# Clock.net
KiCad netlist of a schematic drawn in Altium Designer
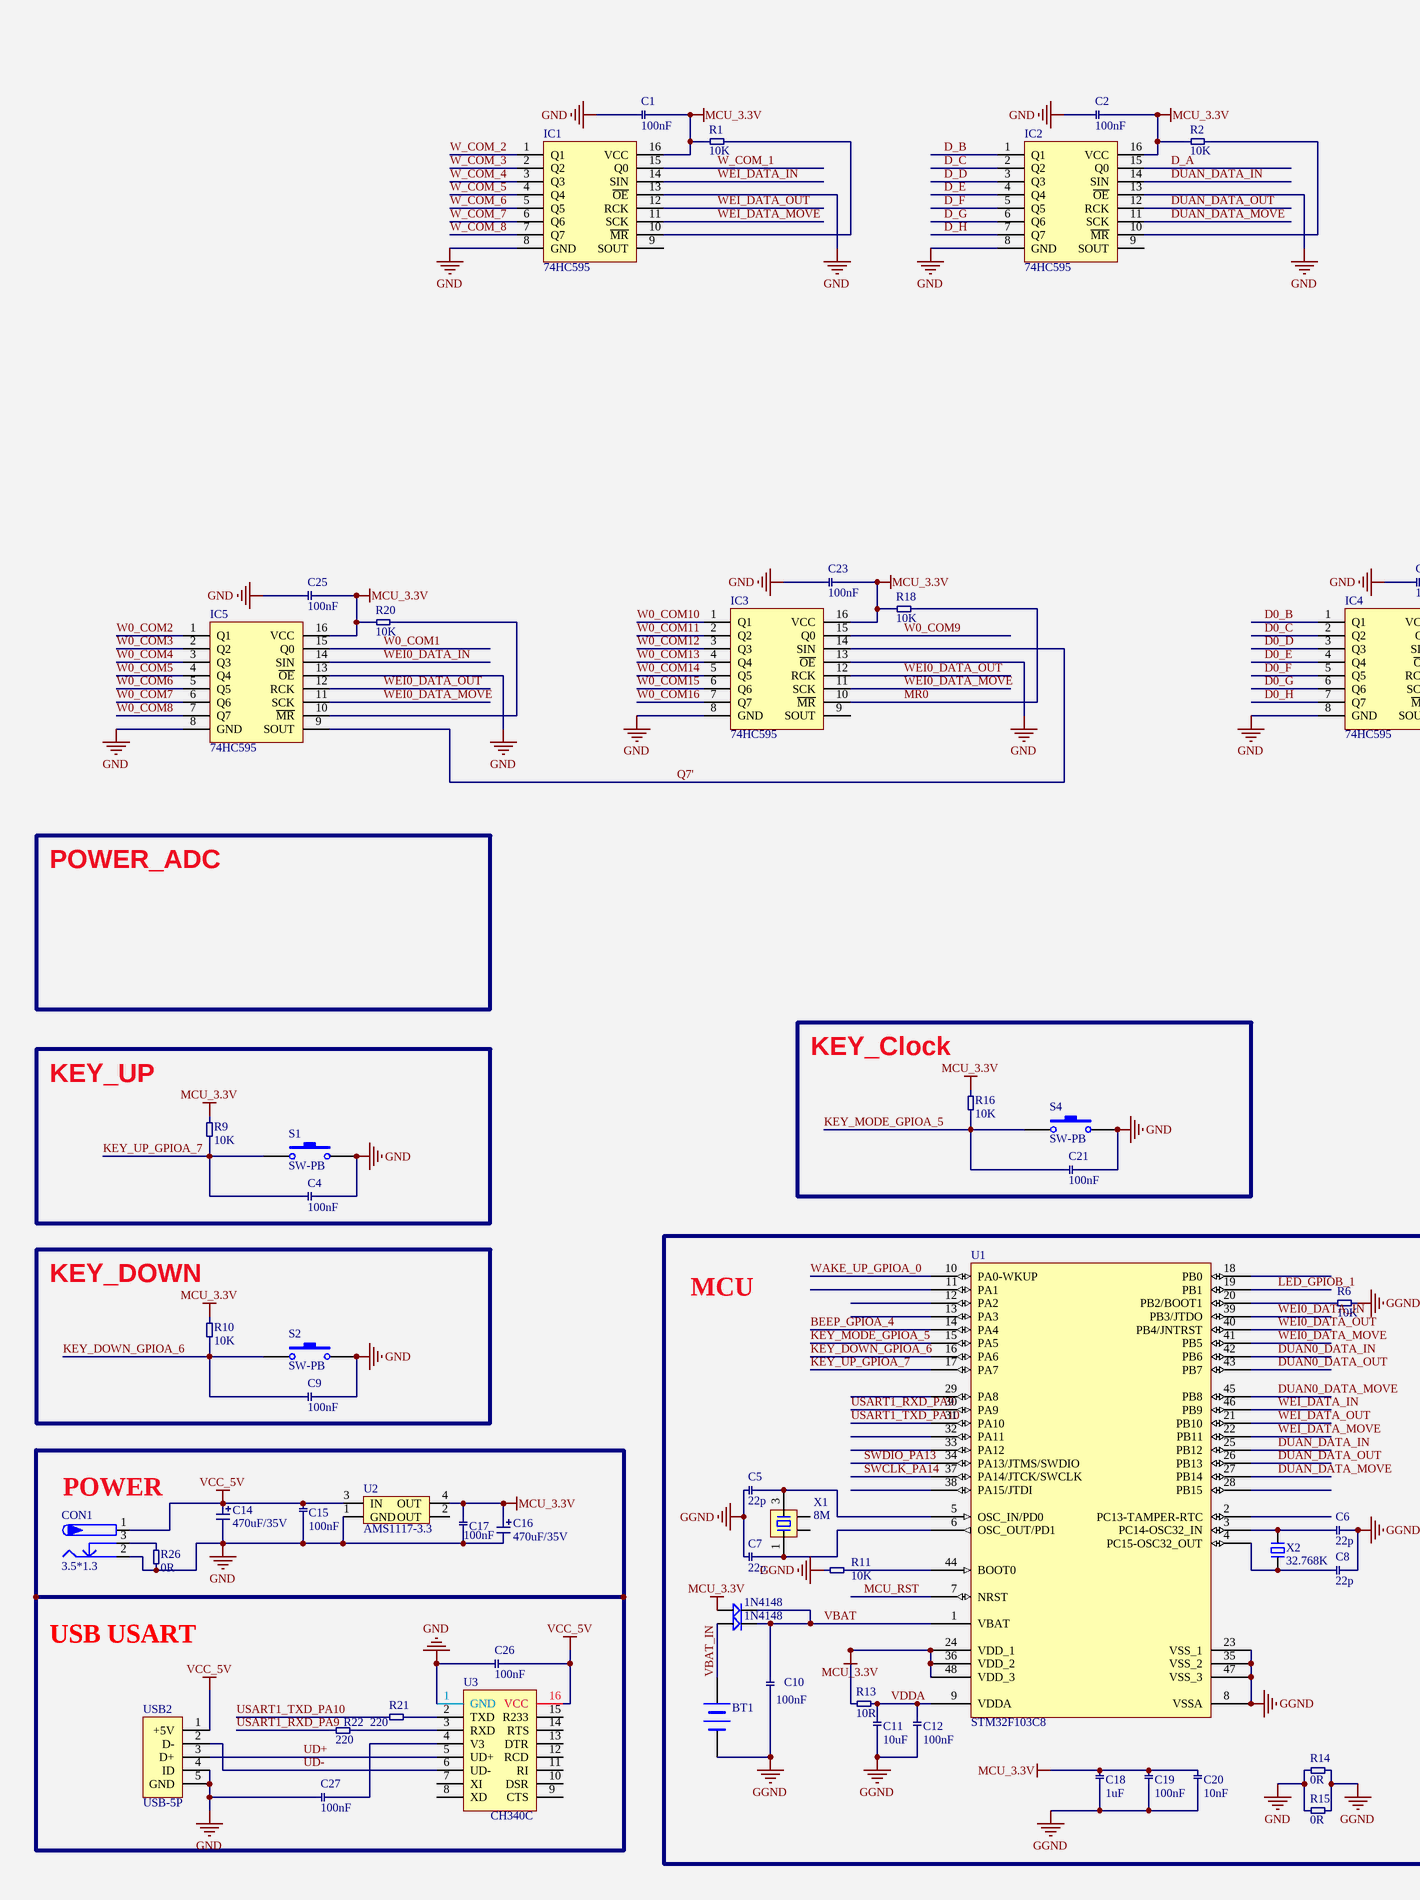
[diagram p0: Clock.SchDoc, left]
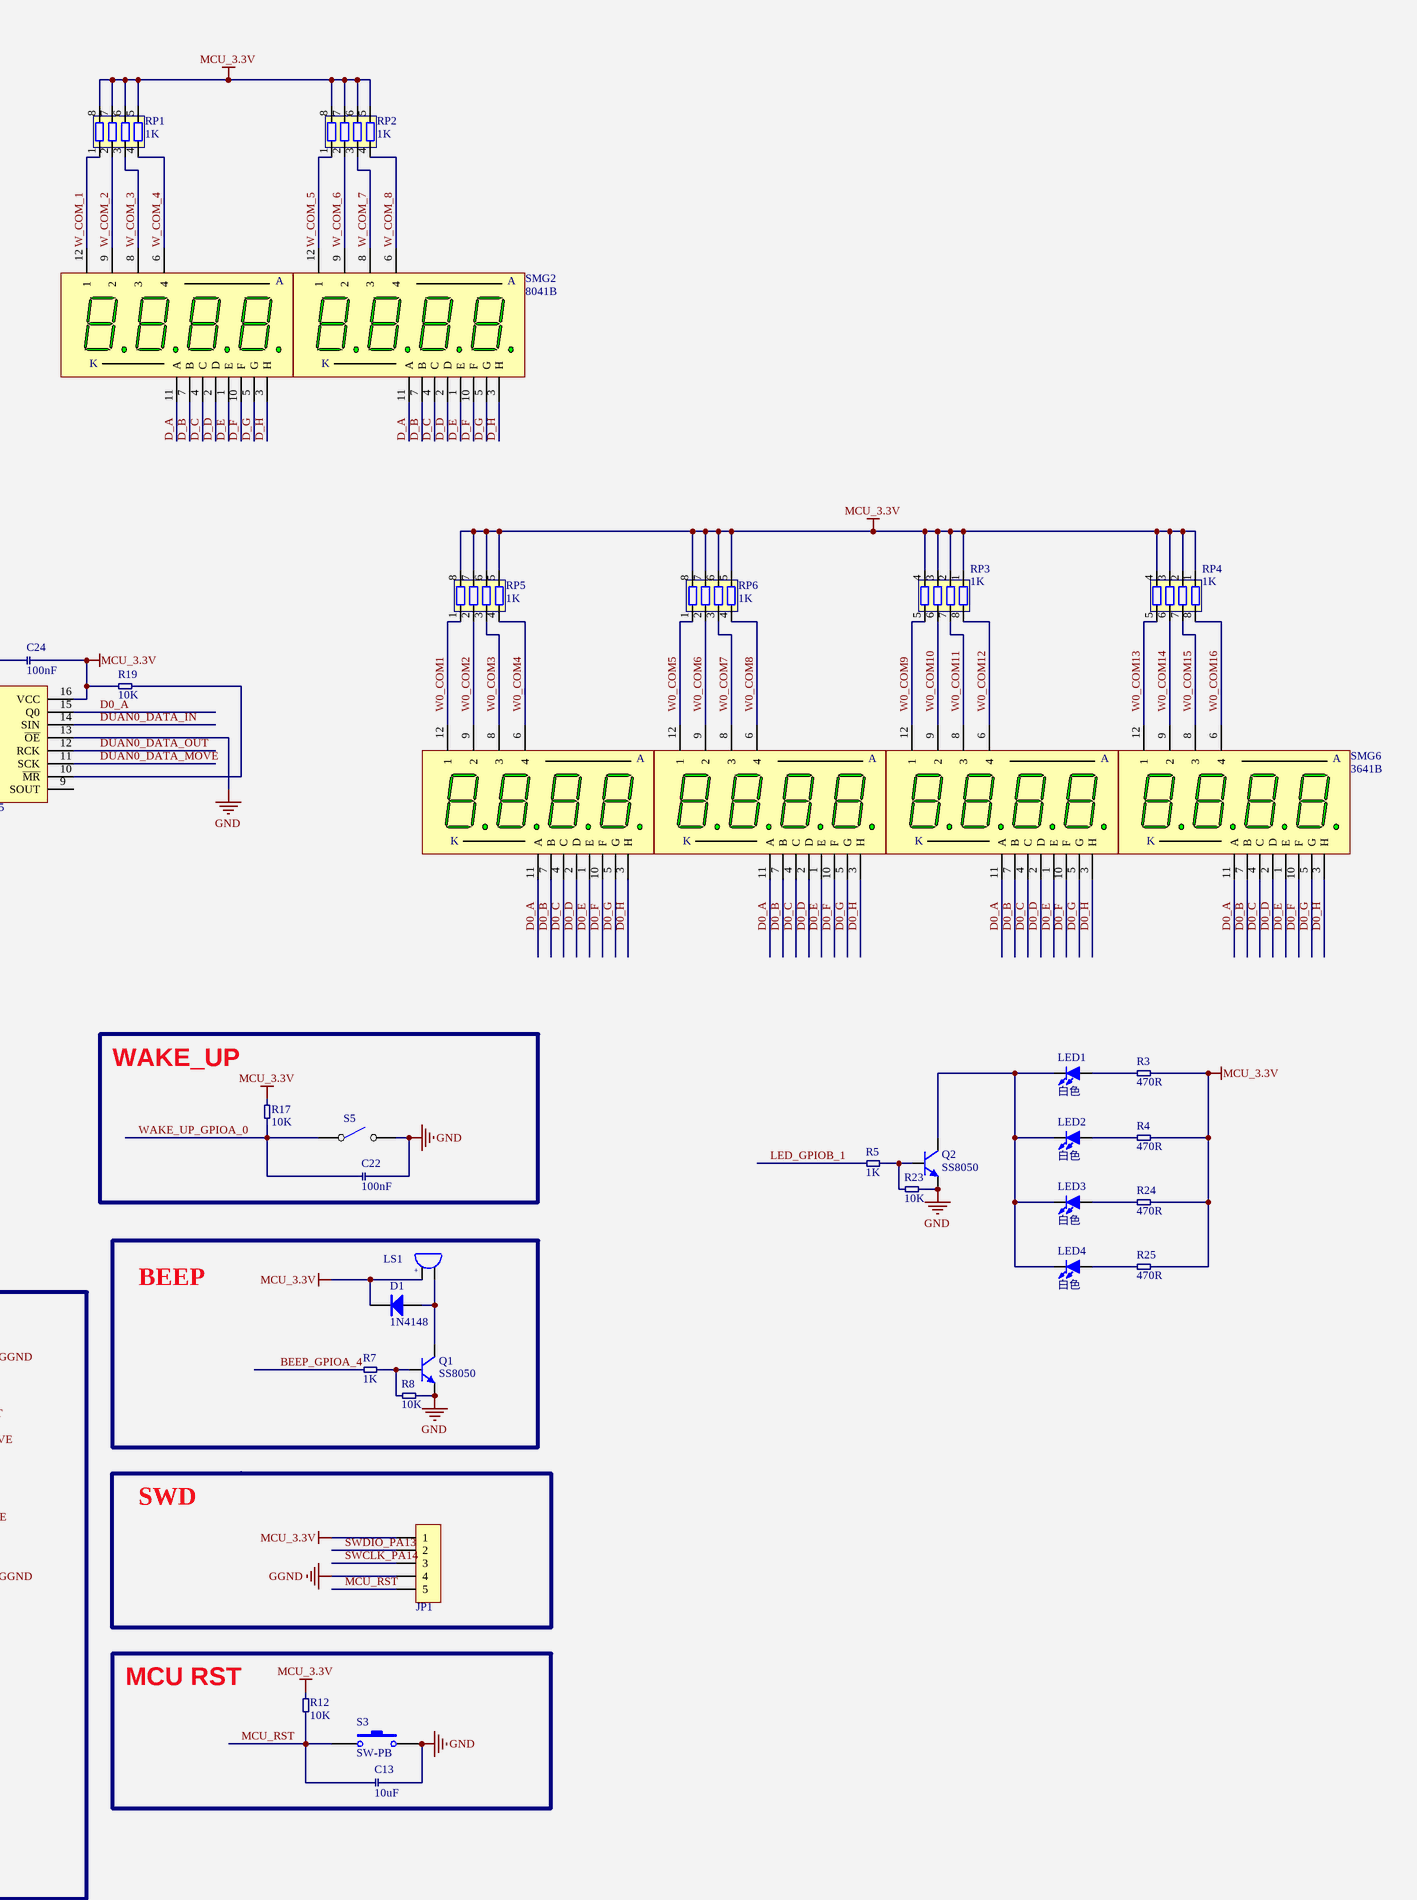
[diagram p1: Clock.SchDoc, right]

(export (version "E")
  (design (tool "Eeschema 10.0.6"))
  (components
    (comp (ref "BT1")
      (value "BATTERY")
      (footprint "VBAT")
      (description "Battery")
      (libsource (lib "杂元件库") (part "BATTERY"))
    )
    (comp (ref "C1") (value "100nF") (footprint "0603CC") (libsource (lib "LFZ@WLP") (part "cap")))
    (comp (ref "C2") (value "100nF") (footprint "0603CC") (libsource (lib "LFZ@WLP") (part "cap")))
    (comp (ref "C4") (value "100nF") (footprint "0603CC") (libsource (lib "LFZ@WLP") (part "cap")))
    (comp (ref "C5") (value "22p") (footprint "0603CC") (libsource (lib "LFZ@WLP") (part "cap")))
    (comp (ref "C6") (value "22p") (footprint "0603CC") (libsource (lib "LFZ@WLP") (part "cap")))
    (comp (ref "C7") (value "22p") (footprint "0603CC") (libsource (lib "LFZ@WLP") (part "cap")))
    (comp (ref "C8") (value "22p") (footprint "0603CC") (libsource (lib "LFZ@WLP") (part "cap")))
    (comp (ref "C9") (value "100nF") (footprint "0603CC") (libsource (lib "LFZ@WLP") (part "cap")))
    (comp (ref "C10") (value "100nF") (footprint "0603CC") (libsource (lib "LFZ@WLP") (part "cap")))
    (comp (ref "C11") (value "10uF") (footprint "0603CC") (libsource (lib "LFZ@WLP") (part "cap")))
    (comp (ref "C12") (value "100nF") (footprint "0603CC") (libsource (lib "LFZ@WLP") (part "cap")))
    (comp (ref "C13") (value "10uF") (footprint "0603CC") (libsource (lib "LFZ@WLP") (part "cap")))
    (comp (ref "C14") (value "470uF/35V") (footprint "CD A(3216)") (libsource (lib "LFZ@WLP") (part "Ecap")))
    (comp (ref "C15") (value "100nF") (footprint "0603CC") (libsource (lib "LFZ@WLP") (part "cap")))
    (comp (ref "C16") (value "470uF/35V") (footprint "C3216") (libsource (lib "LFZ@WLP") (part "Ecap")))
    (comp (ref "C17") (value "100nF") (footprint "0603CC") (libsource (lib "LFZ@WLP") (part "cap")))
    (comp (ref "C18") (value "1uF") (footprint "0603CC") (libsource (lib "LFZ@WLP") (part "cap")))
    (comp (ref "C19") (value "100nF") (footprint "0603CC") (libsource (lib "LFZ@WLP") (part "cap")))
    (comp (ref "C20") (value "10nF") (footprint "0603CC") (libsource (lib "LFZ@WLP") (part "cap")))
    (comp (ref "C21") (value "100nF") (footprint "0603CC") (libsource (lib "LFZ@WLP") (part "cap")))
    (comp (ref "C22") (value "100nF") (footprint "0603CC") (libsource (lib "LFZ@WLP") (part "cap")))
    (comp (ref "C23") (value "100nF") (footprint "0603CC") (libsource (lib "LFZ@WLP") (part "cap")))
    (comp (ref "C24") (value "100nF") (footprint "0603CC") (libsource (lib "LFZ@WLP") (part "cap")))
    (comp (ref "C25") (value "100nF") (footprint "0603CC") (libsource (lib "LFZ@WLP") (part "cap")))
    (comp (ref "C26") (value "100nF") (footprint "0603CC") (libsource (lib "LFZ@WLP") (part "cap")))
    (comp (ref "C27") (value "100nF") (footprint "0603CC") (libsource (lib "LFZ@WLP") (part "cap")))
    (comp (ref "CON1")
      (value "3.5*1.3")
      (footprint "DC-012")
      (description "低压电源接口")
      (fields (field (name "版权归属") "源创客"))
      (libsource (lib "4.1   - 接口类") (part "P-DC"))
    )
    (comp (ref "D1")
      (value "1N4148")
      (footprint "SOD-323")
      (description "高速开关二极管")
      (fields (field (name "版权归属") "源创客"))
      (libsource (lib "8.1   - 二极管-整流桥") (part "1N4148"))
    )
    (comp (ref "D2")
      (value "1N4148")
      (footprint "SOD-323")
      (libsource (lib "WarShip V3 STM32103封装库") (part "D"))
    )
    (comp (ref "D4")
      (value "1N4148")
      (footprint "SOD-323")
      (libsource (lib "WarShip V3 STM32103封装库") (part "D"))
    )
    (comp (ref "IC1")
      (value "74HC595")
      (footprint "SOP16_N")
      (description "8位移位寄存器")
      (fields (field (name "版权归属") "源创客"))
      (libsource (lib "1.2   - 74系列芯片") (part "74HC595"))
    )
    (comp (ref "IC2")
      (value "74HC595")
      (footprint "SOP16_N")
      (description "8位移位寄存器")
      (fields (field (name "版权归属") "源创客"))
      (libsource (lib "1.2   - 74系列芯片") (part "74HC595"))
    )
    (comp (ref "IC3")
      (value "74HC595")
      (footprint "SOP16_N")
      (description "8位移位寄存器")
      (fields (field (name "版权归属") "源创客"))
      (libsource (lib "1.2   - 74系列芯片") (part "74HC595"))
    )
    (comp (ref "IC4")
      (value "74HC595")
      (footprint "SOP16_N")
      (description "8位移位寄存器")
      (fields (field (name "版权归属") "源创客"))
      (libsource (lib "1.2   - 74系列芯片") (part "74HC595"))
    )
    (comp (ref "IC5")
      (value "74HC595")
      (footprint "SOP16_N")
      (description "8位移位寄存器")
      (fields (field (name "版权归属") "源创客"))
      (libsource (lib "1.2   - 74系列芯片") (part "74HC595"))
    )
    (comp (ref "JP1")
      (value "HDR-1X5")
      (footprint "HDR2.54-LI-5P")
      (description "5P接插件")
      (fields (field (name "版权归属") "源创客"))
      (libsource (lib "4.5   - 接插件-脚距2.54") (part "Header 5"))
    )
    (comp (ref "LED1")
      (value "白色")
      (footprint "LED 5MM-W")
      (description "5mm插件LED")
      (fields (field (name "版权归属") "源创客"))
      (libsource (lib "9.1   - LED") (part "LED-5MM"))
    )
    (comp (ref "LED2")
      (value "白色")
      (footprint "LED 5MM-W")
      (description "5mm插件LED")
      (fields (field (name "版权归属") "源创客"))
      (libsource (lib "9.1   - LED") (part "LED-5MM"))
    )
    (comp (ref "LED3")
      (value "白色")
      (footprint "LED 5MM-W")
      (description "5mm插件LED")
      (fields (field (name "版权归属") "源创客"))
      (libsource (lib "9.1   - LED") (part "LED-5MM"))
    )
    (comp (ref "LED4")
      (value "白色")
      (footprint "LED 5MM-W")
      (description "5mm插件LED")
      (fields (field (name "版权归属") "源创客"))
      (libsource (lib "9.1   - LED") (part "LED-5MM"))
    )
    (comp (ref "LS1")
      (value "DC5V")
      (footprint "BEEP 5x9x5.5")
      (description "蜂鸣器")
      (fields (field (name "版权归属") "源创客"))
      (libsource (lib "15.1 - 未分类器件") (part "BEEP"))
    )
    (comp (ref "Q1")
      (value "SS8050")
      (footprint "SOT23-3N")
      (description "高频放大-NPN型")
      (fields (field (name "版权归属") "源创客"))
      (libsource (lib "6.2   - 三极管") (part "8050-SMD"))
    )
    (comp (ref "Q2")
      (value "SS8050")
      (footprint "SOT23-3N")
      (description "高频放大-NPN型")
      (fields (field (name "版权归属") "源创客"))
      (libsource (lib "6.2   - 三极管") (part "8050-SMD"))
    )
    (comp (ref "R1") (value "10K") (footprint "0603RR") (libsource (lib "LFZ@WLP") (part "res")))
    (comp (ref "R2") (value "10K") (footprint "0603RR") (libsource (lib "LFZ@WLP") (part "res")))
    (comp (ref "R3") (value "470R") (footprint "0603RR") (libsource (lib "LFZ@WLP") (part "res")))
    (comp (ref "R4") (value "470R") (footprint "0603RR") (libsource (lib "LFZ@WLP") (part "res")))
    (comp (ref "R5") (value "1K") (footprint "0603RR") (libsource (lib "LFZ@WLP") (part "res")))
    (comp (ref "R6") (value "10K") (footprint "0603RR") (libsource (lib "LFZ@WLP") (part "res")))
    (comp (ref "R7") (value "1K") (footprint "0603RR") (libsource (lib "LFZ@WLP") (part "res")))
    (comp (ref "R8") (value "10K") (footprint "0603RR") (libsource (lib "LFZ@WLP") (part "res")))
    (comp (ref "R9") (value "10K") (footprint "0603RR") (libsource (lib "LFZ@WLP") (part "res")))
    (comp (ref "R10") (value "10K") (footprint "0603RR") (libsource (lib "LFZ@WLP") (part "res")))
    (comp (ref "R11") (value "10K") (footprint "0603RR") (libsource (lib "LFZ@WLP") (part "res")))
    (comp (ref "R12") (value "10K") (footprint "0603RR") (libsource (lib "LFZ@WLP") (part "res")))
    (comp (ref "R13") (value "10R") (footprint "0603RR") (libsource (lib "LFZ@WLP") (part "res")))
    (comp (ref "R14") (value "0R") (footprint "0603RR") (libsource (lib "LFZ@WLP") (part "res")))
    (comp (ref "R15") (value "0R") (footprint "0603RR") (libsource (lib "LFZ@WLP") (part "res")))
    (comp (ref "R16") (value "10K") (footprint "0603RR") (libsource (lib "LFZ@WLP") (part "res")))
    (comp (ref "R17") (value "10K") (footprint "0603RR") (libsource (lib "LFZ@WLP") (part "res")))
    (comp (ref "R18") (value "10K") (footprint "0603RR") (libsource (lib "LFZ@WLP") (part "res")))
    (comp (ref "R19") (value "10K") (footprint "0603RR") (libsource (lib "LFZ@WLP") (part "res")))
    (comp (ref "R20") (value "10K") (footprint "0603RR") (libsource (lib "LFZ@WLP") (part "res")))
    (comp (ref "R21") (value "220") (footprint "0603RR") (libsource (lib "LFZ@WLP") (part "res")))
    (comp (ref "R22") (value "220") (footprint "0603RR") (libsource (lib "LFZ@WLP") (part "res")))
    (comp (ref "R23") (value "10K") (footprint "0603RR") (libsource (lib "LFZ@WLP") (part "res")))
    (comp (ref "R24") (value "470R") (footprint "0603RR") (libsource (lib "LFZ@WLP") (part "res")))
    (comp (ref "R25") (value "470R") (footprint "0603RR") (libsource (lib "LFZ@WLP") (part "res")))
    (comp (ref "R26") (value "0R") (footprint "0603RR") (libsource (lib "LFZ@WLP") (part "res")))
    (comp (ref "RP1")
      (value "1K")
      (footprint "RCA-8P4R-0603")
      (libsource (lib "LFZ@WLP") (part "Resistor_Pack"))
    )
    (comp (ref "RP2")
      (value "1K")
      (footprint "RCA-8P4R-0603")
      (libsource (lib "LFZ@WLP") (part "Resistor_Pack"))
    )
    (comp (ref "RP3") (value "1K") (footprint "RCA-8P4R-0603") (libsource (lib "") (part "Resistor_Pack_1")))
    (comp (ref "RP4") (value "1K") (footprint "RCA-8P4R-0603") (libsource (lib "") (part "Resistor_Pack_1")))
    (comp (ref "RP5")
      (value "1K")
      (footprint "RCA-8P4R-0603")
      (libsource (lib "LFZ@WLP") (part "Resistor_Pack"))
    )
    (comp (ref "RP6")
      (value "1K")
      (footprint "RCA-8P4R-0603")
      (libsource (lib "LFZ@WLP") (part "Resistor_Pack"))
    )
    (comp (ref "S1")
      (value "SW-PB")
      (footprint "TSW DIP-6*6*6_V")
      (description "Switch")
      (fields (field (name "PUBLISHER") "Altium Limited"))
      (libsource (lib "开关及电源") (part "SW-PB"))
    )
    (comp (ref "S2")
      (value "SW-PB")
      (footprint "TSW DIP-6*6*6_V")
      (description "Switch")
      (fields (field (name "PUBLISHER") "Altium Limited"))
      (libsource (lib "开关及电源") (part "SW-PB"))
    )
    (comp (ref "S3")
      (value "SW-PB")
      (footprint "TSW DIP-6*6*6_V")
      (description "Switch")
      (fields (field (name "PUBLISHER") "Altium Limited"))
      (libsource (lib "开关及电源") (part "SW-PB"))
    )
    (comp (ref "S4")
      (value "SW-PB")
      (footprint "TSW DIP-6*6*6_V")
      (description "Switch")
      (fields (field (name "PUBLISHER") "Altium Limited"))
      (libsource (lib "开关及电源") (part "SW-PB"))
    )
    (comp (ref "S5") (value "单刀开关") (footprint "CAP 2.5*5*11-H") (libsource (lib "开关") (part "单刀开关")))
    (comp (ref "SMG1")
      (value "8041B")
      (footprint "SMG 0.8-4P")
      (description "0.8寸4位共阳数码管")
      (fields (field (name "版权归属") "源创客"))
      (libsource (lib "9.2   - 显示器件") (part "8041B"))
    )
    (comp (ref "SMG2")
      (value "8041B")
      (footprint "SMG 0.8-4P")
      (description "0.8寸4位共阳数码管")
      (fields (field (name "版权归属") "源创客"))
      (libsource (lib "9.2   - 显示器件") (part "8041B"))
    )
    (comp (ref "SMG3")
      (value "3641B")
      (footprint "SMG 0.36-4P")
      (description "0.36寸4位共阳数码管")
      (fields (field (name "版权归属") "源创客"))
      (libsource (lib "9.2   - 显示器件") (part "3641B"))
    )
    (comp (ref "SMG4")
      (value "3641B")
      (footprint "SMG 0.36-4P")
      (description "0.36寸4位共阳数码管")
      (fields (field (name "版权归属") "源创客"))
      (libsource (lib "9.2   - 显示器件") (part "3641B"))
    )
    (comp (ref "SMG5")
      (value "3641B")
      (footprint "SMG 0.36-4P")
      (description "0.36寸4位共阳数码管")
      (fields (field (name "版权归属") "源创客"))
      (libsource (lib "9.2   - 显示器件") (part "3641B"))
    )
    (comp (ref "SMG6")
      (value "3641B")
      (footprint "SMG 0.36-4P")
      (description "0.36寸4位共阳数码管")
      (fields (field (name "版权归属") "源创客"))
      (libsource (lib "9.2   - 显示器件") (part "3641B"))
    )
    (comp (ref "U1")
      (value "STM32F103C8")
      (footprint "LQFP48 7X7_M")
      (description "Flaah:64/RAM:20/IO:36")
      (fields (field (name "版权归属") "源创客"))
      (libsource (lib "2.1   - STM32系列单片机") (part "STM32F103C8"))
    )
    (comp (ref "U2")
      (value "AMS1117-3.3")
      (footprint "SOT223_N")
      (libsource (lib "WarShip V3 STM32103封装库") (part "AMS1117"))
    )
    (comp (ref "U3") (value "CH340C") (footprint "SOP16_L") (libsource (lib "LFZ@WLP") (part "CH340C")))
    (comp (ref "USB2")
      (value "USB-5P")
      (footprint "USB-MICRO_C")
      (description "微型USB母座")
      (fields (field (name "版权归属") "源创客"))
      (libsource (lib "4.1   - 接口类") (part "USB-5P"))
    )
    (comp (ref "X1")
      (value "8M")
      (footprint "OSC 3225-4P")
      (description "4脚无源晶振")
      (fields (field (name "版权归属") "源创客"))
      (libsource (lib "10.1 - 保险丝-晶振") (part "XTAL-4P"))
    )
    (comp (ref "X2")
      (value "32.768K")
      (footprint "OSC 3215-2P")
      (description "2脚无源脚晶振")
      (fields (field (name "版权归属") "源创客"))
      (libsource (lib "10.1 - 保险丝-晶振") (part "XTAL-2P"))
    )
  )
  (nets
    (net (code "1") (name "/BEEP_GPIOA_4") (class "Default")
      (node (ref "R7") (pin "1") (pinfunction "1_1") (pintype "passive"))
      (node (ref "U1") (pin "14") (pinfunction "PA4_14") (pintype "bidirectional"))
    )
    (net (code "2") (name "/D0_A") (class "Default")
      (node (ref "IC4") (pin "15") (pinfunction "Q0_15") (pintype "passive"))
      (node (ref "SMG3") (pin "11") (pinfunction "A_11") (pintype "passive"))
      (node (ref "SMG4") (pin "11") (pinfunction "A_11") (pintype "passive"))
      (node (ref "SMG5") (pin "11") (pinfunction "A_11") (pintype "passive"))
      (node (ref "SMG6") (pin "11") (pinfunction "A_11") (pintype "passive"))
    )
    (net (code "3") (name "/D0_B") (class "Default")
      (node (ref "IC4") (pin "1") (pinfunction "Q1_1") (pintype "passive"))
      (node (ref "SMG3") (pin "7") (pinfunction "B_7") (pintype "passive"))
      (node (ref "SMG4") (pin "7") (pinfunction "B_7") (pintype "passive"))
      (node (ref "SMG5") (pin "7") (pinfunction "B_7") (pintype "passive"))
      (node (ref "SMG6") (pin "7") (pinfunction "B_7") (pintype "passive"))
    )
    (net (code "4") (name "/D0_C") (class "Default")
      (node (ref "IC4") (pin "2") (pinfunction "Q2_2") (pintype "passive"))
      (node (ref "SMG3") (pin "4") (pinfunction "C_4") (pintype "passive"))
      (node (ref "SMG4") (pin "4") (pinfunction "C_4") (pintype "passive"))
      (node (ref "SMG5") (pin "4") (pinfunction "C_4") (pintype "passive"))
      (node (ref "SMG6") (pin "4") (pinfunction "C_4") (pintype "passive"))
    )
    (net (code "5") (name "/D0_D") (class "Default")
      (node (ref "IC4") (pin "3") (pinfunction "Q3_3") (pintype "passive"))
      (node (ref "SMG3") (pin "2") (pinfunction "D_2") (pintype "passive"))
      (node (ref "SMG4") (pin "2") (pinfunction "D_2") (pintype "passive"))
      (node (ref "SMG5") (pin "2") (pinfunction "D_2") (pintype "passive"))
      (node (ref "SMG6") (pin "2") (pinfunction "D_2") (pintype "passive"))
    )
    (net (code "6") (name "/D0_E") (class "Default")
      (node (ref "IC4") (pin "4") (pinfunction "Q4_4") (pintype "passive"))
      (node (ref "SMG3") (pin "1") (pinfunction "E_1") (pintype "passive"))
      (node (ref "SMG4") (pin "1") (pinfunction "E_1") (pintype "passive"))
      (node (ref "SMG5") (pin "1") (pinfunction "E_1") (pintype "passive"))
      (node (ref "SMG6") (pin "1") (pinfunction "E_1") (pintype "passive"))
    )
    (net (code "7") (name "/D0_F") (class "Default")
      (node (ref "IC4") (pin "5") (pinfunction "Q5_5") (pintype "passive"))
      (node (ref "SMG3") (pin "10") (pinfunction "F_10") (pintype "passive"))
      (node (ref "SMG4") (pin "10") (pinfunction "F_10") (pintype "passive"))
      (node (ref "SMG5") (pin "10") (pinfunction "F_10") (pintype "passive"))
      (node (ref "SMG6") (pin "10") (pinfunction "F_10") (pintype "passive"))
    )
    (net (code "8") (name "/D0_G") (class "Default")
      (node (ref "IC4") (pin "6") (pinfunction "Q6_6") (pintype "passive"))
      (node (ref "SMG3") (pin "5") (pinfunction "G_5") (pintype "passive"))
      (node (ref "SMG4") (pin "5") (pinfunction "G_5") (pintype "passive"))
      (node (ref "SMG5") (pin "5") (pinfunction "G_5") (pintype "passive"))
      (node (ref "SMG6") (pin "5") (pinfunction "G_5") (pintype "passive"))
    )
    (net (code "9") (name "/D0_H") (class "Default")
      (node (ref "IC4") (pin "7") (pinfunction "Q7_7") (pintype "passive"))
      (node (ref "SMG3") (pin "3") (pinfunction "H_3") (pintype "passive"))
      (node (ref "SMG4") (pin "3") (pinfunction "H_3") (pintype "passive"))
      (node (ref "SMG5") (pin "3") (pinfunction "H_3") (pintype "passive"))
      (node (ref "SMG6") (pin "3") (pinfunction "H_3") (pintype "passive"))
    )
    (net (code "10") (name "/DUAN0_DATA_IN") (class "Default")
      (node (ref "IC4") (pin "14") (pinfunction "SIN_14") (pintype "passive"))
      (node (ref "U1") (pin "42") (pinfunction "PB6_42") (pintype "bidirectional"))
    )
    (net (code "11") (name "/DUAN0_DATA_MOVE") (class "Default")
      (node (ref "IC4") (pin "11") (pinfunction "SCK_11") (pintype "passive"))
      (node (ref "U1") (pin "45") (pinfunction "PB8_45") (pintype "bidirectional"))
    )
    (net (code "12") (name "/DUAN0_DATA_OUT") (class "Default")
      (node (ref "IC4") (pin "12") (pinfunction "RCK_12") (pintype "passive"))
      (node (ref "U1") (pin "43") (pinfunction "PB7_43") (pintype "bidirectional"))
    )
    (net (code "13") (name "/DUAN_DATA_IN") (class "Default")
      (node (ref "IC2") (pin "14") (pinfunction "SIN_14") (pintype "passive"))
      (node (ref "U1") (pin "25") (pinfunction "PB12_25") (pintype "bidirectional"))
    )
    (net (code "14") (name "/DUAN_DATA_MOVE") (class "Default")
      (node (ref "IC2") (pin "11") (pinfunction "SCK_11") (pintype "passive"))
      (node (ref "U1") (pin "27") (pinfunction "PB14_27") (pintype "bidirectional"))
    )
    (net (code "15") (name "/DUAN_DATA_OUT") (class "Default")
      (node (ref "IC2") (pin "12") (pinfunction "RCK_12") (pintype "passive"))
      (node (ref "U1") (pin "26") (pinfunction "PB13_26") (pintype "bidirectional"))
    )
    (net (code "16") (name "/D_A") (class "Default")
      (node (ref "IC2") (pin "15") (pinfunction "Q0_15") (pintype "passive"))
      (node (ref "SMG1") (pin "11") (pinfunction "A_11") (pintype "passive"))
      (node (ref "SMG2") (pin "11") (pinfunction "A_11") (pintype "passive"))
    )
    (net (code "17") (name "/D_B") (class "Default")
      (node (ref "IC2") (pin "1") (pinfunction "Q1_1") (pintype "passive"))
      (node (ref "SMG1") (pin "7") (pinfunction "B_7") (pintype "passive"))
      (node (ref "SMG2") (pin "7") (pinfunction "B_7") (pintype "passive"))
    )
    (net (code "18") (name "/D_C") (class "Default")
      (node (ref "IC2") (pin "2") (pinfunction "Q2_2") (pintype "passive"))
      (node (ref "SMG1") (pin "4") (pinfunction "C_4") (pintype "passive"))
      (node (ref "SMG2") (pin "4") (pinfunction "C_4") (pintype "passive"))
    )
    (net (code "19") (name "/D_D") (class "Default")
      (node (ref "IC2") (pin "3") (pinfunction "Q3_3") (pintype "passive"))
      (node (ref "SMG1") (pin "2") (pinfunction "D_2") (pintype "passive"))
      (node (ref "SMG2") (pin "2") (pinfunction "D_2") (pintype "passive"))
    )
    (net (code "20") (name "/D_E") (class "Default")
      (node (ref "IC2") (pin "4") (pinfunction "Q4_4") (pintype "passive"))
      (node (ref "SMG1") (pin "1") (pinfunction "E_1") (pintype "passive"))
      (node (ref "SMG2") (pin "1") (pinfunction "E_1") (pintype "passive"))
    )
    (net (code "21") (name "/D_F") (class "Default")
      (node (ref "IC2") (pin "5") (pinfunction "Q5_5") (pintype "passive"))
      (node (ref "SMG1") (pin "10") (pinfunction "F_10") (pintype "passive"))
      (node (ref "SMG2") (pin "10") (pinfunction "F_10") (pintype "passive"))
    )
    (net (code "22") (name "/D_G") (class "Default")
      (node (ref "IC2") (pin "6") (pinfunction "Q6_6") (pintype "passive"))
      (node (ref "SMG1") (pin "5") (pinfunction "G_5") (pintype "passive"))
      (node (ref "SMG2") (pin "5") (pinfunction "G_5") (pintype "passive"))
    )
    (net (code "23") (name "/D_H") (class "Default")
      (node (ref "IC2") (pin "7") (pinfunction "Q7_7") (pintype "passive"))
      (node (ref "SMG1") (pin "3") (pinfunction "H_3") (pintype "passive"))
      (node (ref "SMG2") (pin "3") (pinfunction "H_3") (pintype "passive"))
    )
    (net (code "24") (name "/KEY_DOWN_GPIOA_6") (class "Default")
      (node (ref "C9") (pin "1") (pinfunction "1_1") (pintype "passive"))
      (node (ref "R10") (pin "1") (pinfunction "1_1") (pintype "passive"))
      (node (ref "S2") (pin "1") (pinfunction "1_1") (pintype "passive"))
      (node (ref "U1") (pin "16") (pinfunction "PA6_16") (pintype "bidirectional"))
    )
    (net (code "25") (name "/KEY_MODE_GPIOA_5") (class "Default")
      (node (ref "C21") (pin "1") (pinfunction "1_1") (pintype "passive"))
      (node (ref "R16") (pin "1") (pinfunction "1_1") (pintype "passive"))
      (node (ref "S4") (pin "1") (pinfunction "1_1") (pintype "passive"))
      (node (ref "U1") (pin "15") (pinfunction "PA5_15") (pintype "bidirectional"))
    )
    (net (code "26") (name "/KEY_UP_GPIOA_7") (class "Default")
      (node (ref "C4") (pin "1") (pinfunction "1_1") (pintype "passive"))
      (node (ref "R9") (pin "1") (pinfunction "1_1") (pintype "passive"))
      (node (ref "S1") (pin "1") (pinfunction "1_1") (pintype "passive"))
      (node (ref "U1") (pin "17") (pinfunction "PA7_17") (pintype "bidirectional"))
    )
    (net (code "27") (name "/LED_GPIOB_1") (class "Default")
      (node (ref "R5") (pin "1") (pinfunction "1_1") (pintype "passive"))
      (node (ref "U1") (pin "19") (pinfunction "PB1_19") (pintype "bidirectional"))
    )
    (net (code "28") (name "/MCU_RST") (class "Default")
      (node (ref "C13") (pin "2") (pinfunction "2_2") (pintype "passive"))
      (node (ref "JP1") (pin "5") (pinfunction "5_5") (pintype "passive"))
      (node (ref "R12") (pin "1") (pinfunction "1_1") (pintype "passive"))
      (node (ref "S3") (pin "1") (pinfunction "1_1") (pintype "passive"))
      (node (ref "U1") (pin "7") (pinfunction "NRST_7") (pintype "bidirectional"))
    )
    (net (code "29") (name "/MR0") (class "Default")
      (node (ref "IC3") (pin "10") (pinfunction "~{MR}_10") (pintype "passive"))
      (node (ref "R18") (pin "1") (pinfunction "1_1") (pintype "passive"))
    )
    (net (code "30") (name "/Q7'") (class "Default")
      (node (ref "IC3") (pin "14") (pinfunction "SIN_14") (pintype "passive"))
      (node (ref "IC5") (pin "9") (pinfunction "SOUT_9") (pintype "passive"))
    )
    (net (code "31") (name "/SWCLK_PA14") (class "Default")
      (node (ref "JP1") (pin "3") (pinfunction "3_3") (pintype "passive"))
      (node (ref "U1") (pin "37") (pinfunction "PA14/JTCK/SWCLK_37") (pintype "bidirectional"))
    )
    (net (code "32") (name "/SWDIO_PA13") (class "Default")
      (node (ref "JP1") (pin "2") (pinfunction "2_2") (pintype "passive"))
      (node (ref "U1") (pin "34") (pinfunction "PA13/JTMS/SWDIO_34") (pintype "bidirectional"))
    )
    (net (code "33") (name "/UD+") (class "Default")
      (node (ref "U3") (pin "5") (pinfunction "UD+_5") (pintype "passive"))
      (node (ref "USB2") (pin "3") (pinfunction "D+_3") (pintype "passive"))
    )
    (net (code "34") (name "/UD-") (class "Default")
      (node (ref "U3") (pin "6") (pinfunction "UD-_6") (pintype "passive"))
      (node (ref "USB2") (pin "2") (pinfunction "D-_2") (pintype "passive"))
    )
    (net (code "35") (name "/USART1_RXD_PA9") (class "Default")
      (node (ref "R22") (pin "1") (pinfunction "1_1") (pintype "passive"))
      (node (ref "U1") (pin "30") (pinfunction "PA9_30") (pintype "bidirectional"))
    )
    (net (code "36") (name "/USART1_TXD_PA10") (class "Default")
      (node (ref "R21") (pin "1") (pinfunction "1_1") (pintype "passive"))
      (node (ref "U1") (pin "31") (pinfunction "PA10_31") (pintype "bidirectional"))
    )
    (net (code "37") (name "/VBAT") (class "Default")
      (node (ref "C10") (pin "2") (pinfunction "2_2") (pintype "passive"))
      (node (ref "D2") (pin "2") (pintype "passive"))
      (node (ref "D4") (pin "2") (pintype "passive"))
      (node (ref "U1") (pin "1") (pinfunction "VBAT_1") (pintype "power_in"))
    )
    (net (code "38") (name "/VBAT_IN") (class "Default")
      (node (ref "BT1") (pin "1") (pinfunction "+_1") (pintype "passive"))
      (node (ref "D2") (pin "1") (pintype "passive"))
    )
    (net (code "39") (name "/VDDA") (class "Default")
      (node (ref "C11") (pin "2") (pinfunction "2_2") (pintype "passive"))
      (node (ref "C12") (pin "2") (pinfunction "2_2") (pintype "passive"))
      (node (ref "R13") (pin "2") (pinfunction "2_2") (pintype "passive"))
      (node (ref "U1") (pin "9") (pinfunction "VDDA_9") (pintype "power_in"))
    )
    (net (code "40") (name "/W0_COM1") (class "Default")
      (node (ref "IC5") (pin "15") (pinfunction "Q0_15") (pintype "passive"))
      (node (ref "RP5") (pin "1") (pinfunction "1_1") (pintype "passive"))
      (node (ref "SMG3") (pin "12") (pinfunction "1_12") (pintype "passive"))
    )
    (net (code "41") (name "/W0_COM2") (class "Default")
      (node (ref "IC5") (pin "1") (pinfunction "Q1_1") (pintype "passive"))
      (node (ref "RP5") (pin "2") (pinfunction "2_2") (pintype "passive"))
      (node (ref "SMG3") (pin "9") (pinfunction "2_9") (pintype "passive"))
    )
    (net (code "42") (name "/W0_COM3") (class "Default")
      (node (ref "IC5") (pin "2") (pinfunction "Q2_2") (pintype "passive"))
      (node (ref "RP5") (pin "3") (pinfunction "3_3") (pintype "passive"))
      (node (ref "SMG3") (pin "8") (pinfunction "3_8") (pintype "passive"))
    )
    (net (code "43") (name "/W0_COM4") (class "Default")
      (node (ref "IC5") (pin "3") (pinfunction "Q3_3") (pintype "passive"))
      (node (ref "RP5") (pin "4") (pinfunction "4_4") (pintype "passive"))
      (node (ref "SMG3") (pin "6") (pinfunction "4_6") (pintype "passive"))
    )
    (net (code "44") (name "/W0_COM5") (class "Default")
      (node (ref "IC5") (pin "4") (pinfunction "Q4_4") (pintype "passive"))
      (node (ref "RP6") (pin "1") (pinfunction "1_1") (pintype "passive"))
      (node (ref "SMG4") (pin "12") (pinfunction "1_12") (pintype "passive"))
    )
    (net (code "45") (name "/W0_COM6") (class "Default")
      (node (ref "IC5") (pin "5") (pinfunction "Q5_5") (pintype "passive"))
      (node (ref "RP6") (pin "2") (pinfunction "2_2") (pintype "passive"))
      (node (ref "SMG4") (pin "9") (pinfunction "2_9") (pintype "passive"))
    )
    (net (code "46") (name "/W0_COM7") (class "Default")
      (node (ref "IC5") (pin "6") (pinfunction "Q6_6") (pintype "passive"))
      (node (ref "RP6") (pin "3") (pinfunction "3_3") (pintype "passive"))
      (node (ref "SMG4") (pin "8") (pinfunction "3_8") (pintype "passive"))
    )
    (net (code "47") (name "/W0_COM8") (class "Default")
      (node (ref "IC5") (pin "7") (pinfunction "Q7_7") (pintype "passive"))
      (node (ref "RP6") (pin "4") (pinfunction "4_4") (pintype "passive"))
      (node (ref "SMG4") (pin "6") (pinfunction "4_6") (pintype "passive"))
    )
    (net (code "48") (name "/W0_COM9") (class "Default")
      (node (ref "IC3") (pin "15") (pinfunction "Q0_15") (pintype "passive"))
      (node (ref "RP3") (pin "5") (pinfunction "5_5") (pintype "passive"))
      (node (ref "SMG5") (pin "12") (pinfunction "1_12") (pintype "passive"))
    )
    (net (code "49") (name "/W0_COM10") (class "Default")
      (node (ref "IC3") (pin "1") (pinfunction "Q1_1") (pintype "passive"))
      (node (ref "RP3") (pin "6") (pinfunction "6_6") (pintype "passive"))
      (node (ref "SMG5") (pin "9") (pinfunction "2_9") (pintype "passive"))
    )
    (net (code "50") (name "/W0_COM11") (class "Default")
      (node (ref "IC3") (pin "2") (pinfunction "Q2_2") (pintype "passive"))
      (node (ref "RP3") (pin "7") (pinfunction "7_7") (pintype "passive"))
      (node (ref "SMG5") (pin "8") (pinfunction "3_8") (pintype "passive"))
    )
    (net (code "51") (name "/W0_COM12") (class "Default")
      (node (ref "IC3") (pin "3") (pinfunction "Q3_3") (pintype "passive"))
      (node (ref "RP3") (pin "8") (pinfunction "8_8") (pintype "passive"))
      (node (ref "SMG5") (pin "6") (pinfunction "4_6") (pintype "passive"))
    )
    (net (code "52") (name "/W0_COM13") (class "Default")
      (node (ref "IC3") (pin "4") (pinfunction "Q4_4") (pintype "passive"))
      (node (ref "RP4") (pin "5") (pinfunction "5_5") (pintype "passive"))
      (node (ref "SMG6") (pin "12") (pinfunction "1_12") (pintype "passive"))
    )
    (net (code "53") (name "/W0_COM14") (class "Default")
      (node (ref "IC3") (pin "5") (pinfunction "Q5_5") (pintype "passive"))
      (node (ref "RP4") (pin "6") (pinfunction "6_6") (pintype "passive"))
      (node (ref "SMG6") (pin "9") (pinfunction "2_9") (pintype "passive"))
    )
    (net (code "54") (name "/W0_COM15") (class "Default")
      (node (ref "IC3") (pin "6") (pinfunction "Q6_6") (pintype "passive"))
      (node (ref "RP4") (pin "7") (pinfunction "7_7") (pintype "passive"))
      (node (ref "SMG6") (pin "8") (pinfunction "3_8") (pintype "passive"))
    )
    (net (code "55") (name "/W0_COM16") (class "Default")
      (node (ref "IC3") (pin "7") (pinfunction "Q7_7") (pintype "passive"))
      (node (ref "RP4") (pin "8") (pinfunction "8_8") (pintype "passive"))
      (node (ref "SMG6") (pin "6") (pinfunction "4_6") (pintype "passive"))
    )
    (net (code "56") (name "/WAKE_UP_GPIOA_0") (class "Default")
      (node (ref "C22") (pin "1") (pinfunction "1_1") (pintype "passive"))
      (node (ref "R17") (pin "1") (pinfunction "1_1") (pintype "passive"))
      (node (ref "S5") (pin "1") (pinfunction "1_1") (pintype "passive"))
      (node (ref "U1") (pin "10") (pinfunction "PA0-WKUP_10") (pintype "bidirectional"))
    )
    (net (code "57") (name "/WEI0_DATA_IN") (class "Default")
      (node (ref "IC5") (pin "14") (pinfunction "SIN_14") (pintype "passive"))
      (node (ref "U1") (pin "39") (pinfunction "PB3/JTDO_39") (pintype "bidirectional"))
    )
    (net (code "58") (name "/WEI0_DATA_MOVE") (class "Default")
      (node (ref "IC3") (pin "11") (pinfunction "SCK_11") (pintype "passive"))
      (node (ref "IC5") (pin "11") (pinfunction "SCK_11") (pintype "passive"))
      (node (ref "U1") (pin "41") (pinfunction "PB5_41") (pintype "bidirectional"))
    )
    (net (code "59") (name "/WEI0_DATA_OUT") (class "Default")
      (node (ref "IC3") (pin "12") (pinfunction "RCK_12") (pintype "passive"))
      (node (ref "IC5") (pin "12") (pinfunction "RCK_12") (pintype "passive"))
      (node (ref "U1") (pin "40") (pinfunction "PB4/JNTRST_40") (pintype "bidirectional"))
    )
    (net (code "60") (name "/WEI_DATA_IN") (class "Default")
      (node (ref "IC1") (pin "14") (pinfunction "SIN_14") (pintype "passive"))
      (node (ref "U1") (pin "46") (pinfunction "PB9_46") (pintype "bidirectional"))
    )
    (net (code "61") (name "/WEI_DATA_MOVE") (class "Default")
      (node (ref "IC1") (pin "11") (pinfunction "SCK_11") (pintype "passive"))
      (node (ref "U1") (pin "22") (pinfunction "PB11_22") (pintype "bidirectional"))
    )
    (net (code "62") (name "/WEI_DATA_OUT") (class "Default")
      (node (ref "IC1") (pin "12") (pinfunction "RCK_12") (pintype "passive"))
      (node (ref "U1") (pin "21") (pinfunction "PB10_21") (pintype "bidirectional"))
    )
    (net (code "63") (name "/W_COM_1") (class "Default")
      (node (ref "IC1") (pin "15") (pinfunction "Q0_15") (pintype "passive"))
      (node (ref "RP1") (pin "1") (pinfunction "1_1") (pintype "passive"))
      (node (ref "SMG1") (pin "12") (pinfunction "1_12") (pintype "passive"))
    )
    (net (code "64") (name "/W_COM_2") (class "Default")
      (node (ref "IC1") (pin "1") (pinfunction "Q1_1") (pintype "passive"))
      (node (ref "RP1") (pin "2") (pinfunction "2_2") (pintype "passive"))
      (node (ref "SMG1") (pin "9") (pinfunction "2_9") (pintype "passive"))
    )
    (net (code "65") (name "/W_COM_3") (class "Default")
      (node (ref "IC1") (pin "2") (pinfunction "Q2_2") (pintype "passive"))
      (node (ref "RP1") (pin "3") (pinfunction "3_3") (pintype "passive"))
      (node (ref "SMG1") (pin "8") (pinfunction "3_8") (pintype "passive"))
    )
    (net (code "66") (name "/W_COM_4") (class "Default")
      (node (ref "IC1") (pin "3") (pinfunction "Q3_3") (pintype "passive"))
      (node (ref "RP1") (pin "4") (pinfunction "4_4") (pintype "passive"))
      (node (ref "SMG1") (pin "6") (pinfunction "4_6") (pintype "passive"))
    )
    (net (code "67") (name "/W_COM_5") (class "Default")
      (node (ref "IC1") (pin "4") (pinfunction "Q4_4") (pintype "passive"))
      (node (ref "RP2") (pin "1") (pinfunction "1_1") (pintype "passive"))
      (node (ref "SMG2") (pin "12") (pinfunction "1_12") (pintype "passive"))
    )
    (net (code "68") (name "/W_COM_6") (class "Default")
      (node (ref "IC1") (pin "5") (pinfunction "Q5_5") (pintype "passive"))
      (node (ref "RP2") (pin "2") (pinfunction "2_2") (pintype "passive"))
      (node (ref "SMG2") (pin "9") (pinfunction "2_9") (pintype "passive"))
    )
    (net (code "69") (name "/W_COM_7") (class "Default")
      (node (ref "IC1") (pin "6") (pinfunction "Q6_6") (pintype "passive"))
      (node (ref "RP2") (pin "3") (pinfunction "3_3") (pintype "passive"))
      (node (ref "SMG2") (pin "8") (pinfunction "3_8") (pintype "passive"))
    )
    (net (code "70") (name "/W_COM_8") (class "Default")
      (node (ref "IC1") (pin "7") (pinfunction "Q7_7") (pintype "passive"))
      (node (ref "RP2") (pin "4") (pinfunction "4_4") (pintype "passive"))
      (node (ref "SMG2") (pin "6") (pinfunction "4_6") (pintype "passive"))
    )
    (net (code "71") (name "GGND") (class "Default")
      (node (ref "BT1") (pin "2") (pinfunction "-_2") (pintype "passive"))
      (node (ref "C10") (pin "1") (pinfunction "1_1") (pintype "passive"))
      (node (ref "C11") (pin "1") (pinfunction "1_1") (pintype "passive"))
      (node (ref "C12") (pin "1") (pinfunction "1_1") (pintype "passive"))
      (node (ref "C18") (pin "1") (pinfunction "1_1") (pintype "passive"))
      (node (ref "C19") (pin "1") (pinfunction "1_1") (pintype "passive"))
      (node (ref "C20") (pin "1") (pinfunction "1_1") (pintype "passive"))
      (node (ref "C5") (pin "1") (pinfunction "1_1") (pintype "passive"))
      (node (ref "C6") (pin "2") (pinfunction "2_2") (pintype "passive"))
      (node (ref "C7") (pin "1") (pinfunction "1_1") (pintype "passive"))
      (node (ref "C8") (pin "2") (pinfunction "2_2") (pintype "passive"))
      (node (ref "JP1") (pin "4") (pinfunction "4_4") (pintype "passive"))
      (node (ref "R11") (pin "1") (pinfunction "1_1") (pintype "passive"))
      (node (ref "R14") (pin "2") (pinfunction "2_2") (pintype "passive"))
      (node (ref "R15") (pin "2") (pinfunction "2_2") (pintype "passive"))
      (node (ref "R6") (pin "2") (pinfunction "2_2") (pintype "passive"))
      (node (ref "U1") (pin "23") (pinfunction "VSS_1_23") (pintype "power_in"))
      (node (ref "U1") (pin "35") (pinfunction "VSS_2_35") (pintype "power_in"))
      (node (ref "U1") (pin "47") (pinfunction "VSS_3_47") (pintype "power_in"))
      (node (ref "U1") (pin "8") (pinfunction "VSSA_8") (pintype "power_in"))
    )
    (net (code "72") (name "GND") (class "Default")
      (node (ref "C1") (pin "2") (pinfunction "2_2") (pintype "passive"))
      (node (ref "C13") (pin "1") (pinfunction "1_1") (pintype "passive"))
      (node (ref "C14") (pin "2") (pinfunction "2_2") (pintype "passive"))
      (node (ref "C15") (pin "1") (pinfunction "1_1") (pintype "passive"))
      (node (ref "C16") (pin "2") (pinfunction "2_2") (pintype "passive"))
      (node (ref "C17") (pin "1") (pinfunction "1_1") (pintype "passive"))
      (node (ref "C2") (pin "2") (pinfunction "2_2") (pintype "passive"))
      (node (ref "C21") (pin "2") (pinfunction "2_2") (pintype "passive"))
      (node (ref "C22") (pin "2") (pinfunction "2_2") (pintype "passive"))
      (node (ref "C23") (pin "2") (pinfunction "2_2") (pintype "passive"))
      (node (ref "C24") (pin "2") (pinfunction "2_2") (pintype "passive"))
      (node (ref "C25") (pin "2") (pinfunction "2_2") (pintype "passive"))
      (node (ref "C26") (pin "2") (pinfunction "2_2") (pintype "passive"))
      (node (ref "C27") (pin "2") (pinfunction "2_2") (pintype "passive"))
      (node (ref "C4") (pin "2") (pinfunction "2_2") (pintype "passive"))
      (node (ref "C9") (pin "2") (pinfunction "2_2") (pintype "passive"))
      (node (ref "CON1") (pin "2") (pintype "power_in"))
      (node (ref "IC1") (pin "13") (pinfunction "~{OE}_13") (pintype "passive"))
      (node (ref "IC1") (pin "8") (pinfunction "GND_8") (pintype "passive"))
      (node (ref "IC2") (pin "13") (pinfunction "~{OE}_13") (pintype "passive"))
      (node (ref "IC2") (pin "8") (pinfunction "GND_8") (pintype "passive"))
      (node (ref "IC3") (pin "13") (pinfunction "~{OE}_13") (pintype "passive"))
      (node (ref "IC3") (pin "8") (pinfunction "GND_8") (pintype "passive"))
      (node (ref "IC4") (pin "13") (pinfunction "~{OE}_13") (pintype "passive"))
      (node (ref "IC4") (pin "8") (pinfunction "GND_8") (pintype "passive"))
      (node (ref "IC5") (pin "13") (pinfunction "~{OE}_13") (pintype "passive"))
      (node (ref "IC5") (pin "8") (pinfunction "GND_8") (pintype "passive"))
      (node (ref "Q1") (pin "2") (pinfunction "E_2") (pintype "passive"))
      (node (ref "Q2") (pin "2") (pinfunction "E_2") (pintype "passive"))
      (node (ref "R14") (pin "1") (pinfunction "1_1") (pintype "passive"))
      (node (ref "R15") (pin "1") (pinfunction "1_1") (pintype "passive"))
      (node (ref "R23") (pin "2") (pinfunction "2_2") (pintype "passive"))
      (node (ref "R26") (pin "2") (pinfunction "2_2") (pintype "passive"))
      (node (ref "R8") (pin "2") (pinfunction "2_2") (pintype "passive"))
      (node (ref "S1") (pin "2") (pinfunction "2_2") (pintype "passive"))
      (node (ref "S2") (pin "2") (pinfunction "2_2") (pintype "passive"))
      (node (ref "S3") (pin "2") (pinfunction "2_2") (pintype "passive"))
      (node (ref "S4") (pin "2") (pinfunction "2_2") (pintype "passive"))
      (node (ref "S5") (pin "2") (pinfunction "2_2") (pintype "passive"))
      (node (ref "U2") (pin "1") (pinfunction "GND_1") (pintype "passive"))
      (node (ref "U3") (pin "1") (pinfunction "GND_1") (pintype "passive"))
      (node (ref "USB2") (pin "4") (pinfunction "ID_4") (pintype "passive"))
      (node (ref "USB2") (pin "5") (pinfunction "GND_5") (pintype "passive"))
    )
    (net (code "73") (name "MCU_3.3V") (class "Default")
      (node (ref "C1") (pin "1") (pinfunction "1_1") (pintype "passive"))
      (node (ref "C16") (pin "1") (pinfunction "1_1") (pintype "passive"))
      (node (ref "C17") (pin "2") (pinfunction "2_2") (pintype "passive"))
      (node (ref "C18") (pin "2") (pinfunction "2_2") (pintype "passive"))
      (node (ref "C19") (pin "2") (pinfunction "2_2") (pintype "passive"))
      (node (ref "C2") (pin "1") (pinfunction "1_1") (pintype "passive"))
      (node (ref "C20") (pin "2") (pinfunction "2_2") (pintype "passive"))
      (node (ref "C23") (pin "1") (pinfunction "1_1") (pintype "passive"))
      (node (ref "C24") (pin "1") (pinfunction "1_1") (pintype "passive"))
      (node (ref "C25") (pin "1") (pinfunction "1_1") (pintype "passive"))
      (node (ref "D1") (pin "2") (pinfunction "K_2") (pintype "passive"))
      (node (ref "D4") (pin "1") (pintype "passive"))
      (node (ref "IC1") (pin "16") (pinfunction "VCC_16") (pintype "passive"))
      (node (ref "IC2") (pin "16") (pinfunction "VCC_16") (pintype "passive"))
      (node (ref "IC3") (pin "16") (pinfunction "VCC_16") (pintype "passive"))
      (node (ref "IC4") (pin "16") (pinfunction "VCC_16") (pintype "passive"))
      (node (ref "IC5") (pin "16") (pinfunction "VCC_16") (pintype "passive"))
      (node (ref "JP1") (pin "1") (pinfunction "1_1") (pintype "passive"))
      (node (ref "LS1") (pin "1") (pinfunction "1_1") (pintype "passive"))
      (node (ref "R1") (pin "2") (pinfunction "2_2") (pintype "passive"))
      (node (ref "R10") (pin "2") (pinfunction "2_2") (pintype "passive"))
      (node (ref "R12") (pin "2") (pinfunction "2_2") (pintype "passive"))
      (node (ref "R13") (pin "1") (pinfunction "1_1") (pintype "passive"))
      (node (ref "R16") (pin "2") (pinfunction "2_2") (pintype "passive"))
      (node (ref "R17") (pin "2") (pinfunction "2_2") (pintype "passive"))
      (node (ref "R18") (pin "2") (pinfunction "2_2") (pintype "passive"))
      (node (ref "R19") (pin "2") (pinfunction "2_2") (pintype "passive"))
      (node (ref "R2") (pin "2") (pinfunction "2_2") (pintype "passive"))
      (node (ref "R20") (pin "2") (pinfunction "2_2") (pintype "passive"))
      (node (ref "R24") (pin "2") (pinfunction "2_2") (pintype "passive"))
      (node (ref "R25") (pin "2") (pinfunction "2_2") (pintype "passive"))
      (node (ref "R3") (pin "2") (pinfunction "2_2") (pintype "passive"))
      (node (ref "R4") (pin "2") (pinfunction "2_2") (pintype "passive"))
      (node (ref "R9") (pin "2") (pinfunction "2_2") (pintype "passive"))
      (node (ref "RP1") (pin "5") (pinfunction "5_5") (pintype "passive"))
      (node (ref "RP1") (pin "6") (pinfunction "6_6") (pintype "passive"))
      (node (ref "RP1") (pin "7") (pinfunction "7_7") (pintype "passive"))
      (node (ref "RP1") (pin "8") (pinfunction "8_8") (pintype "passive"))
      (node (ref "RP2") (pin "5") (pinfunction "5_5") (pintype "passive"))
      (node (ref "RP2") (pin "6") (pinfunction "6_6") (pintype "passive"))
      (node (ref "RP2") (pin "7") (pinfunction "7_7") (pintype "passive"))
      (node (ref "RP2") (pin "8") (pinfunction "8_8") (pintype "passive"))
      (node (ref "RP3") (pin "1") (pinfunction "1_1") (pintype "passive"))
      (node (ref "RP3") (pin "2") (pinfunction "2_2") (pintype "passive"))
      (node (ref "RP3") (pin "3") (pinfunction "3_3") (pintype "passive"))
      (node (ref "RP3") (pin "4") (pinfunction "4_4") (pintype "passive"))
      (node (ref "RP4") (pin "1") (pinfunction "1_1") (pintype "passive"))
      (node (ref "RP4") (pin "2") (pinfunction "2_2") (pintype "passive"))
      (node (ref "RP4") (pin "3") (pinfunction "3_3") (pintype "passive"))
      (node (ref "RP4") (pin "4") (pinfunction "4_4") (pintype "passive"))
      (node (ref "RP5") (pin "5") (pinfunction "5_5") (pintype "passive"))
      (node (ref "RP5") (pin "6") (pinfunction "6_6") (pintype "passive"))
      (node (ref "RP5") (pin "7") (pinfunction "7_7") (pintype "passive"))
      (node (ref "RP5") (pin "8") (pinfunction "8_8") (pintype "passive"))
      (node (ref "RP6") (pin "5") (pinfunction "5_5") (pintype "passive"))
      (node (ref "RP6") (pin "6") (pinfunction "6_6") (pintype "passive"))
      (node (ref "RP6") (pin "7") (pinfunction "7_7") (pintype "passive"))
      (node (ref "RP6") (pin "8") (pinfunction "8_8") (pintype "passive"))
      (node (ref "U1") (pin "24") (pinfunction "VDD_1_24") (pintype "power_in"))
      (node (ref "U1") (pin "36") (pinfunction "VDD_2_36") (pintype "power_in"))
      (node (ref "U1") (pin "48") (pinfunction "VDD_3_48") (pintype "power_in"))
      (node (ref "U2") (pin "4") (pinfunction "OUT_4") (pintype "passive"))
    )
    (net (code "74") (name "Net-(CON1-Pad3)") (class "Default")
      (node (ref "CON1") (pin "3") (pintype "power_in"))
      (node (ref "R26") (pin "1") (pinfunction "1_1") (pintype "passive"))
    )
    (net (code "75") (name "Net-(D1-A)") (class "Default")
      (node (ref "D1") (pin "1") (pinfunction "A_1") (pintype "passive"))
      (node (ref "LS1") (pin "2") (pinfunction "2_2") (pintype "passive"))
      (node (ref "Q1") (pin "3") (pinfunction "C_3") (pintype "passive"))
    )
    (net (code "76") (name "Net-(IC1-~{MR})") (class "Default")
      (node (ref "IC1") (pin "10") (pinfunction "~{MR}_10") (pintype "passive"))
      (node (ref "R1") (pin "1") (pinfunction "1_1") (pintype "passive"))
    )
    (net (code "77") (name "Net-(IC2-~{MR})") (class "Default")
      (node (ref "IC2") (pin "10") (pinfunction "~{MR}_10") (pintype "passive"))
      (node (ref "R2") (pin "1") (pinfunction "1_1") (pintype "passive"))
    )
    (net (code "78") (name "Net-(IC4-~{MR})") (class "Default")
      (node (ref "IC4") (pin "10") (pinfunction "~{MR}_10") (pintype "passive"))
      (node (ref "R19") (pin "1") (pinfunction "1_1") (pintype "passive"))
    )
    (net (code "79") (name "Net-(IC5-~{MR})") (class "Default")
      (node (ref "IC5") (pin "10") (pinfunction "~{MR}_10") (pintype "passive"))
      (node (ref "R20") (pin "1") (pinfunction "1_1") (pintype "passive"))
    )
    (net (code "80") (name "Net-(LED1-A)") (class "Default")
      (node (ref "LED1") (pin "1") (pinfunction "A_1") (pintype "passive"))
      (node (ref "R3") (pin "1") (pinfunction "1_1") (pintype "passive"))
    )
    (net (code "81") (name "Net-(LED1-K)") (class "Default")
      (node (ref "LED1") (pin "2") (pinfunction "K_2") (pintype "passive"))
      (node (ref "LED2") (pin "2") (pinfunction "K_2") (pintype "passive"))
      (node (ref "LED3") (pin "2") (pinfunction "K_2") (pintype "passive"))
      (node (ref "LED4") (pin "2") (pinfunction "K_2") (pintype "passive"))
      (node (ref "Q2") (pin "3") (pinfunction "C_3") (pintype "passive"))
    )
    (net (code "82") (name "Net-(LED2-A)") (class "Default")
      (node (ref "LED2") (pin "1") (pinfunction "A_1") (pintype "passive"))
      (node (ref "R4") (pin "1") (pinfunction "1_1") (pintype "passive"))
    )
    (net (code "83") (name "Net-(LED3-A)") (class "Default")
      (node (ref "LED3") (pin "1") (pinfunction "A_1") (pintype "passive"))
      (node (ref "R24") (pin "1") (pinfunction "1_1") (pintype "passive"))
    )
    (net (code "84") (name "Net-(LED4-A)") (class "Default")
      (node (ref "LED4") (pin "1") (pinfunction "A_1") (pintype "passive"))
      (node (ref "R25") (pin "1") (pinfunction "1_1") (pintype "passive"))
    )
    (net (code "85") (name "Net-(Q1-B)") (class "Default")
      (node (ref "Q1") (pin "1") (pinfunction "B_1") (pintype "passive"))
      (node (ref "R7") (pin "2") (pinfunction "2_2") (pintype "passive"))
      (node (ref "R8") (pin "1") (pinfunction "1_1") (pintype "passive"))
    )
    (net (code "86") (name "Net-(Q2-B)") (class "Default")
      (node (ref "Q2") (pin "1") (pinfunction "B_1") (pintype "passive"))
      (node (ref "R23") (pin "1") (pinfunction "1_1") (pintype "passive"))
      (node (ref "R5") (pin "2") (pinfunction "2_2") (pintype "passive"))
    )
    (net (code "87") (name "Net-(U1-BOOT0)") (class "Default")
      (node (ref "R11") (pin "2") (pinfunction "2_2") (pintype "passive"))
      (node (ref "U1") (pin "44") (pinfunction "BOOT0_44") (pintype "input"))
    )
    (net (code "88") (name "Net-(U1-OSC_IN{slash}PD0)") (class "Default")
      (node (ref "C5") (pin "2") (pinfunction "2_2") (pintype "passive"))
      (node (ref "U1") (pin "5") (pinfunction "OSC_IN/PD0_5") (pintype "input"))
      (node (ref "X1") (pin "3") (pinfunction "3_3") (pintype "passive"))
    )
    (net (code "89") (name "Net-(U1-OSC_OUT{slash}PD1)") (class "Default")
      (node (ref "C7") (pin "2") (pinfunction "2_2") (pintype "passive"))
      (node (ref "U1") (pin "6") (pinfunction "OSC_OUT/PD1_6") (pintype "output"))
      (node (ref "X1") (pin "1") (pinfunction "1_1") (pintype "passive"))
    )
    (net (code "90") (name "Net-(U1-PB2{slash}BOOT1)") (class "Default")
      (node (ref "R6") (pin "1") (pinfunction "1_1") (pintype "passive"))
      (node (ref "U1") (pin "20") (pinfunction "PB2/BOOT1_20") (pintype "bidirectional"))
    )
    (net (code "91") (name "Net-(U1-PC14-OSC32_IN)") (class "Default")
      (node (ref "C6") (pin "1") (pinfunction "1_1") (pintype "passive"))
      (node (ref "U1") (pin "3") (pinfunction "PC14-OSC32_IN_3") (pintype "bidirectional"))
      (node (ref "X2") (pin "2") (pinfunction "2_2") (pintype "passive"))
    )
    (net (code "92") (name "Net-(U1-PC15-OSC32_OUT)") (class "Default")
      (node (ref "C8") (pin "1") (pinfunction "1_1") (pintype "passive"))
      (node (ref "U1") (pin "4") (pinfunction "PC15-OSC32_OUT_4") (pintype "bidirectional"))
      (node (ref "X2") (pin "1") (pinfunction "1_1") (pintype "passive"))
    )
    (net (code "93") (name "Net-(U3-RXD)") (class "Default")
      (node (ref "R22") (pin "2") (pinfunction "2_2") (pintype "passive"))
      (node (ref "U3") (pin "3") (pinfunction "RXD_3") (pintype "passive"))
    )
    (net (code "94") (name "Net-(U3-TXD)") (class "Default")
      (node (ref "R21") (pin "2") (pinfunction "2_2") (pintype "passive"))
      (node (ref "U3") (pin "2") (pinfunction "TXD_2") (pintype "passive"))
    )
    (net (code "95") (name "Net-(U3-V3)") (class "Default")
      (node (ref "C27") (pin "1") (pinfunction "1_1") (pintype "passive"))
      (node (ref "U3") (pin "4") (pinfunction "V3_4") (pintype "passive"))
    )
    (net (code "96") (name "VCC_5V") (class "Default")
      (node (ref "C14") (pin "1") (pinfunction "1_1") (pintype "passive"))
      (node (ref "C15") (pin "2") (pinfunction "2_2") (pintype "passive"))
      (node (ref "C26") (pin "1") (pinfunction "1_1") (pintype "passive"))
      (node (ref "CON1") (pin "1") (pintype "power_in"))
      (node (ref "U2") (pin "3") (pinfunction "IN_3") (pintype "passive"))
      (node (ref "U3") (pin "16") (pinfunction "VCC_16") (pintype "passive"))
      (node (ref "USB2") (pin "1") (pinfunction "+5V_1") (pintype "passive"))
    )
    (net (code "97") (name "unconnected-(IC1-SOUT-Pad9)") (class "Default")
      (node (ref "IC1") (pin "9") (pinfunction "SOUT_9") (pintype "passive"))
    )
    (net (code "98") (name "unconnected-(IC2-SOUT-Pad9)") (class "Default")
      (node (ref "IC2") (pin "9") (pinfunction "SOUT_9") (pintype "passive"))
    )
    (net (code "99") (name "unconnected-(IC3-SOUT-Pad9)") (class "Default")
      (node (ref "IC3") (pin "9") (pinfunction "SOUT_9") (pintype "passive"))
    )
    (net (code "100") (name "unconnected-(IC4-SOUT-Pad9)") (class "Default")
      (node (ref "IC4") (pin "9") (pinfunction "SOUT_9") (pintype "passive"))
    )
    (net (code "101") (name "unconnected-(U1-PA1-Pad11)") (class "Default")
      (node (ref "U1") (pin "11") (pinfunction "PA1_11") (pintype "bidirectional"))
    )
    (net (code "102") (name "unconnected-(U1-PA2-Pad12)") (class "Default")
      (node (ref "U1") (pin "12") (pinfunction "PA2_12") (pintype "bidirectional"))
    )
    (net (code "103") (name "unconnected-(U1-PA3-Pad13)") (class "Default")
      (node (ref "U1") (pin "13") (pinfunction "PA3_13") (pintype "bidirectional"))
    )
    (net (code "104") (name "unconnected-(U1-PA8-Pad29)") (class "Default")
      (node (ref "U1") (pin "29") (pinfunction "PA8_29") (pintype "bidirectional"))
    )
    (net (code "105") (name "unconnected-(U1-PA11-Pad32)") (class "Default")
      (node (ref "U1") (pin "32") (pinfunction "PA11_32") (pintype "bidirectional"))
    )
    (net (code "106") (name "unconnected-(U1-PA12-Pad33)") (class "Default")
      (node (ref "U1") (pin "33") (pinfunction "PA12_33") (pintype "bidirectional"))
    )
    (net (code "107") (name "unconnected-(U1-PA15{slash}JTDI-Pad38)") (class "Default")
      (node (ref "U1") (pin "38") (pinfunction "PA15/JTDI_38") (pintype "bidirectional"))
    )
    (net (code "108") (name "unconnected-(U1-PB0-Pad18)") (class "Default")
      (node (ref "U1") (pin "18") (pinfunction "PB0_18") (pintype "bidirectional"))
    )
    (net (code "109") (name "unconnected-(U1-PB15-Pad28)") (class "Default")
      (node (ref "U1") (pin "28") (pinfunction "PB15_28") (pintype "bidirectional"))
    )
    (net (code "110") (name "unconnected-(U1-PC13-TAMPER-RTC-Pad2)") (class "Default")
      (node (ref "U1") (pin "2") (pinfunction "PC13-TAMPER-RTC_2") (pintype "bidirectional"))
    )
    (net (code "111") (name "unconnected-(U2-OUT-Pad2)") (class "Default")
      (node (ref "U2") (pin "2") (pinfunction "OUT_2") (pintype "passive"))
    )
    (net (code "112") (name "unconnected-(U3-CTS-Pad9)") (class "Default")
      (node (ref "U3") (pin "9") (pinfunction "CTS_9") (pintype "passive"))
    )
    (net (code "113") (name "unconnected-(U3-DSR-Pad10)") (class "Default")
      (node (ref "U3") (pin "10") (pinfunction "DSR_10") (pintype "passive"))
    )
    (net (code "114") (name "unconnected-(U3-DTR-Pad13)") (class "Default")
      (node (ref "U3") (pin "13") (pinfunction "DTR_13") (pintype "passive"))
    )
    (net (code "115") (name "unconnected-(U3-R233-Pad15)") (class "Default")
      (node (ref "U3") (pin "15") (pinfunction "R233_15") (pintype "passive"))
    )
    (net (code "116") (name "unconnected-(U3-RCD-Pad12)") (class "Default")
      (node (ref "U3") (pin "12") (pinfunction "RCD_12") (pintype "passive"))
    )
    (net (code "117") (name "unconnected-(U3-RI-Pad11)") (class "Default")
      (node (ref "U3") (pin "11") (pinfunction "RI_11") (pintype "passive"))
    )
    (net (code "118") (name "unconnected-(U3-RTS-Pad14)") (class "Default")
      (node (ref "U3") (pin "14") (pinfunction "RTS_14") (pintype "passive"))
    )
    (net (code "119") (name "unconnected-(U3-XD-Pad8)") (class "Default")
      (node (ref "U3") (pin "8") (pinfunction "XD_8") (pintype "passive"))
    )
    (net (code "120") (name "unconnected-(U3-XI-Pad7)") (class "Default")
      (node (ref "U3") (pin "7") (pinfunction "XI_7") (pintype "passive"))
    )
    (net (code "121") (name "unconnected-(X1-Pad2)") (class "Default")
      (node (ref "X1") (pin "2") (pinfunction "2_2") (pintype "passive"))
    )
    (net (code "122") (name "unconnected-(X1-Pad4)") (class "Default")
      (node (ref "X1") (pin "4") (pinfunction "4_4") (pintype "passive"))
    )
  )
)
